# fabflash-mk-2_2-driver.net
KiCad netlist of a schematic drawn in EAGLE
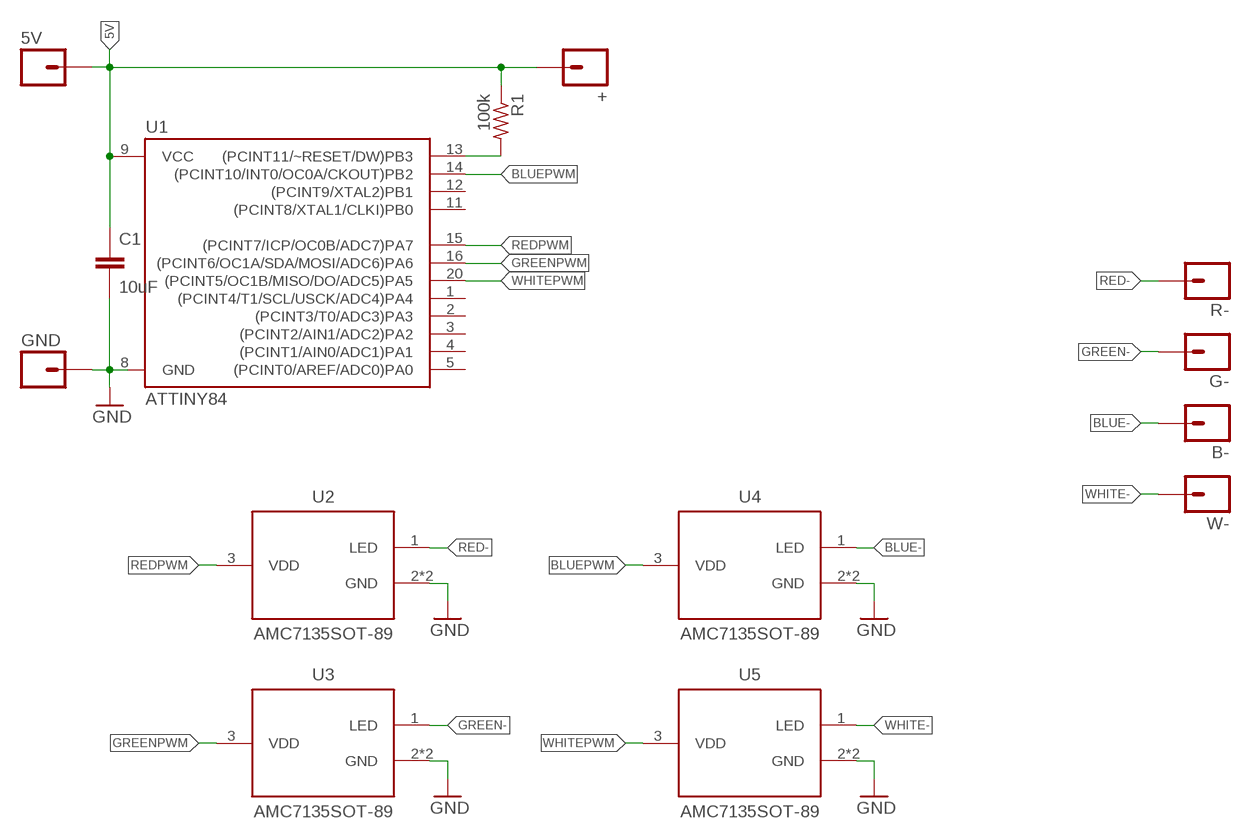
[diagram p0: schematic, sheet 1]

(export (version "E")
  (design (tool "Eeschema 10.0.6"))
  (components
    (comp (ref "+")
      (value "M01SMD_2X3MM")
      (footprint "eagle-import:1X01_SMD_2X3MM")
      (libsource (lib "eagle-import") (part "M01SMD_2X3MM"))
    )
    (comp (ref "5V")
      (value "M01SMD_2X3MM")
      (footprint "eagle-import:1X01_SMD_2X3MM")
      (libsource (lib "eagle-import") (part "M01SMD_2X3MM"))
    )
    (comp (ref "B-")
      (value "M01SMD_2X3MM")
      (footprint "eagle-import:1X01_SMD_2X3MM")
      (libsource (lib "eagle-import") (part "M01SMD_2X3MM"))
    )
    (comp (ref "C1")
      (value "10uF")
      (footprint "eagle-import:C0805")
      (libsource (lib "eagle-import") (part "CAPACITOR-CERAMICC0805"))
    )
    (comp (ref "G-")
      (value "M01SMD_2X3MM")
      (footprint "eagle-import:1X01_SMD_2X3MM")
      (libsource (lib "eagle-import") (part "M01SMD_2X3MM"))
    )
    (comp (ref "GND")
      (value "M01NOT-A-VIA-NOPE")
      (footprint "eagle-import:1X01_NOSILK_NOSTOP")
      (libsource (lib "eagle-import") (part "M01NOT-A-VIA-NOPE"))
    )
    (comp (ref "R-")
      (value "M01SMD_2X3MM")
      (footprint "eagle-import:1X01_SMD_2X3MM")
      (libsource (lib "eagle-import") (part "M01SMD_2X3MM"))
    )
    (comp (ref "R1")
      (value "100k")
      (footprint "eagle-import:R0603")
      (libsource (lib "eagle-import") (part "RESISTORR0603"))
    )
    (comp (ref "U1")
      (value "ATTINY84")
      (footprint "eagle-import:QFN20")
      (libsource (lib "eagle-import") (part "ATTINY84ATTINY84-20MU"))
    )
    (comp (ref "U2")
      (value "AMC7135SOT-89")
      (footprint "eagle-import:SOT89")
      (libsource (lib "eagle-import") (part "AMC7135SOT-89"))
    )
    (comp (ref "U3")
      (value "AMC7135SOT-89")
      (footprint "eagle-import:SOT89")
      (libsource (lib "eagle-import") (part "AMC7135SOT-89"))
    )
    (comp (ref "U4")
      (value "AMC7135SOT-89")
      (footprint "eagle-import:SOT89")
      (libsource (lib "eagle-import") (part "AMC7135SOT-89"))
    )
    (comp (ref "U5")
      (value "AMC7135SOT-89")
      (footprint "eagle-import:SOT89")
      (libsource (lib "eagle-import") (part "AMC7135SOT-89"))
    )
    (comp (ref "W-")
      (value "M01SMD_2X3MM")
      (footprint "eagle-import:1X01_SMD_2X3MM")
      (libsource (lib "eagle-import") (part "M01SMD_2X3MM"))
    )
  )
  (nets
    (net (code "1") (name "5V") (class "Default")
      (node (ref "+") (pin "P$1") (pinfunction "1_P$1") (pintype "passive"))
      (node (ref "5V") (pin "P$1") (pinfunction "1_P$1") (pintype "passive"))
      (node (ref "C1") (pin "1") (pinfunction "1_1") (pintype "passive"))
      (node (ref "R1") (pin "1") (pinfunction "1_1") (pintype "passive"))
      (node (ref "U1") (pin "9") (pinfunction "VCC_9") (pintype "bidirectional"))
    )
    (net (code "2") (name "BLUE-") (class "Default")
      (node (ref "B-") (pin "P$1") (pinfunction "1_P$1") (pintype "passive"))
      (node (ref "U4") (pin "1") (pinfunction "LED_1") (pintype "bidirectional"))
    )
    (net (code "3") (name "BLUEPWM") (class "Default")
      (node (ref "U1") (pin "14") (pinfunction "(PCINT10/INT0/OC0A/CKOUT)PB2_14") (pintype "bidirectional"))
      (node (ref "U4") (pin "3") (pinfunction "VDD_3") (pintype "bidirectional"))
    )
    (net (code "4") (name "GND") (class "Default")
      (node (ref "C1") (pin "2") (pinfunction "2_2") (pintype "passive"))
      (node (ref "GND") (pin "P$1") (pinfunction "1_P$1") (pintype "passive"))
      (node (ref "U1") (pin "8") (pinfunction "GND_8") (pintype "bidirectional"))
      (node (ref "U2") (pin "2") (pinfunction "GND_2") (pintype "bidirectional"))
      (node (ref "U2") (pin "4") (pinfunction "GND_4") (pintype "bidirectional"))
      (node (ref "U3") (pin "2") (pinfunction "GND_2") (pintype "bidirectional"))
      (node (ref "U3") (pin "4") (pinfunction "GND_4") (pintype "bidirectional"))
      (node (ref "U4") (pin "2") (pinfunction "GND_2") (pintype "bidirectional"))
      (node (ref "U4") (pin "4") (pinfunction "GND_4") (pintype "bidirectional"))
      (node (ref "U5") (pin "2") (pinfunction "GND_2") (pintype "bidirectional"))
      (node (ref "U5") (pin "4") (pinfunction "GND_4") (pintype "bidirectional"))
    )
    (net (code "5") (name "GREEN-") (class "Default")
      (node (ref "G-") (pin "P$1") (pinfunction "1_P$1") (pintype "passive"))
      (node (ref "U3") (pin "1") (pinfunction "LED_1") (pintype "bidirectional"))
    )
    (net (code "6") (name "GREENPWM") (class "Default")
      (node (ref "U1") (pin "16") (pinfunction "(PCINT6/OC1A/SDA/MOSI/ADC6)PA6_16") (pintype "bidirectional"))
      (node (ref "U3") (pin "3") (pinfunction "VDD_3") (pintype "bidirectional"))
    )
    (net (code "7") (name "Net-(U1-(PCINT11{slash}~{RESET{slash}DW})PB3)") (class "Default")
      (node (ref "R1") (pin "2") (pinfunction "2_2") (pintype "passive"))
      (node (ref "U1") (pin "13") (pinfunction "(PCINT11/~{RESET/DW})PB3_13") (pintype "bidirectional"))
    )
    (net (code "8") (name "RED-") (class "Default")
      (node (ref "R-") (pin "P$1") (pinfunction "1_P$1") (pintype "passive"))
      (node (ref "U2") (pin "1") (pinfunction "LED_1") (pintype "bidirectional"))
    )
    (net (code "9") (name "REDPWM") (class "Default")
      (node (ref "U1") (pin "15") (pinfunction "(PCINT7/ICP/OC0B/ADC7)PA7_15") (pintype "bidirectional"))
      (node (ref "U2") (pin "3") (pinfunction "VDD_3") (pintype "bidirectional"))
    )
    (net (code "10") (name "WHITE-") (class "Default")
      (node (ref "U5") (pin "1") (pinfunction "LED_1") (pintype "bidirectional"))
      (node (ref "W-") (pin "P$1") (pinfunction "1_P$1") (pintype "passive"))
    )
    (net (code "11") (name "WHITEPWM") (class "Default")
      (node (ref "U1") (pin "20") (pinfunction "(PCINT5/OC1B/MISO/DO/ADC5)PA5_20") (pintype "bidirectional"))
      (node (ref "U5") (pin "3") (pinfunction "VDD_3") (pintype "bidirectional"))
    )
    (net (code "12") (name "unconnected-(U1-(PCINT0{slash}AREF{slash}ADC0)PA0-Pad5)") (class "Default")
      (node (ref "U1") (pin "5") (pinfunction "(PCINT0/AREF/ADC0)PA0_5") (pintype "bidirectional"))
    )
    (net (code "13") (name "unconnected-(U1-(PCINT1{slash}AIN0{slash}ADC1)PA1-Pad4)") (class "Default")
      (node (ref "U1") (pin "4") (pinfunction "(PCINT1/AIN0/ADC1)PA1_4") (pintype "bidirectional"))
    )
    (net (code "14") (name "unconnected-(U1-(PCINT2{slash}AIN1{slash}ADC2)PA2-Pad3)") (class "Default")
      (node (ref "U1") (pin "3") (pinfunction "(PCINT2/AIN1/ADC2)PA2_3") (pintype "bidirectional"))
    )
    (net (code "15") (name "unconnected-(U1-(PCINT3{slash}T0{slash}ADC3)PA3-Pad2)") (class "Default")
      (node (ref "U1") (pin "2") (pinfunction "(PCINT3/T0/ADC3)PA3_2") (pintype "bidirectional"))
    )
    (net (code "16") (name "unconnected-(U1-(PCINT4{slash}T1{slash}SCL{slash}USCK{slash}ADC4)PA4-Pad1)") (class "Default")
      (node (ref "U1") (pin "1") (pinfunction "(PCINT4/T1/SCL/USCK/ADC4)PA4_1") (pintype "bidirectional"))
    )
    (net (code "17") (name "unconnected-(U1-(PCINT8{slash}XTAL1{slash}CLKI)PB0-Pad11)") (class "Default")
      (node (ref "U1") (pin "11") (pinfunction "(PCINT8/XTAL1/CLKI)PB0_11") (pintype "bidirectional"))
    )
    (net (code "18") (name "unconnected-(U1-(PCINT9{slash}XTAL2)PB1-Pad12)") (class "Default")
      (node (ref "U1") (pin "12") (pinfunction "(PCINT9/XTAL2)PB1_12") (pintype "bidirectional"))
    )
  )
)
